# Sheet1.net
KiCad netlist of a schematic drawn in Altium Designer
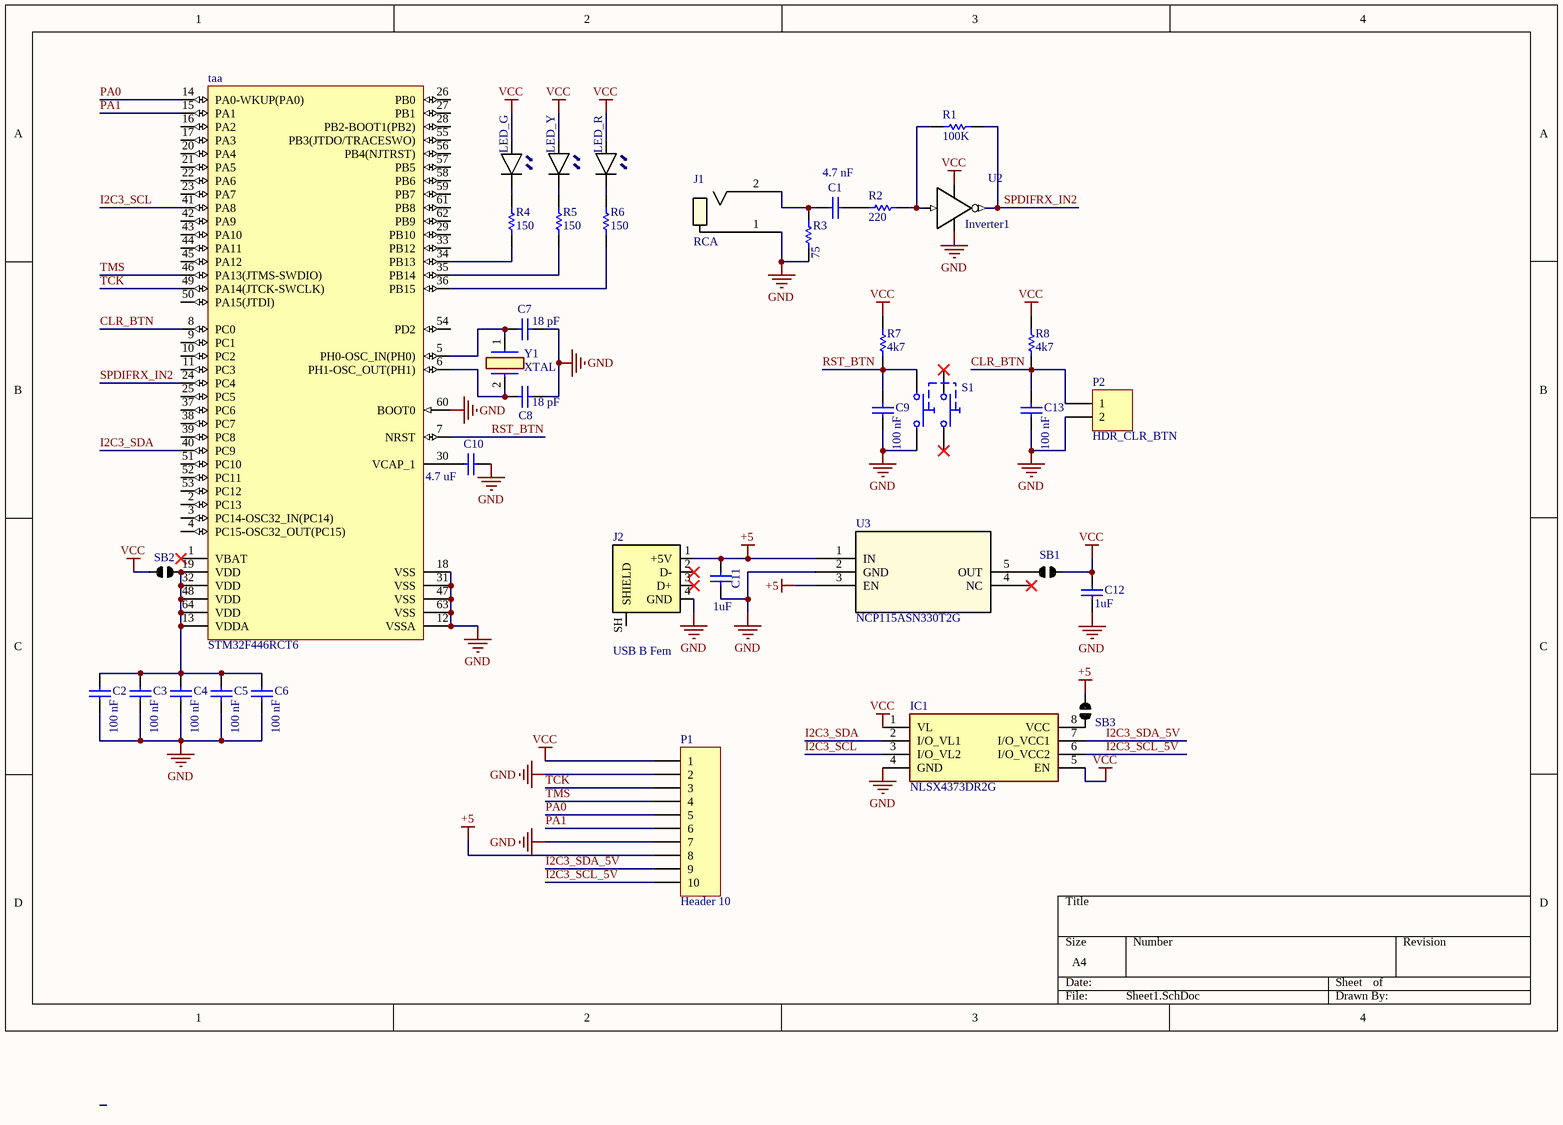
[diagram p0: Sheet1.SchDoc]

(export (version "E")
  (design (tool "Eeschema 10.0.6"))
  (components
    (comp (ref "C1")
      (value "4.7 nF")
      (footprint "RESC3216X70N")
      (description "Capacitor")
      (fields (field (name "Comment") "Cap") (field (name "PUBLISHER") "Altium Limited"))
      (libsource (lib "Miscellaneous Devices") (part "Cap"))
    )
    (comp (ref "C2")
      (value "100 nF")
      (footprint "RESC3216X70N")
      (description "Capacitor")
      (fields (field (name "Comment") "Cap") (field (name "PUBLISHER") "Altium Limited"))
      (libsource (lib "Miscellaneous Devices") (part "Cap"))
    )
    (comp (ref "C3")
      (value "100 nF")
      (footprint "RESC3216X70N")
      (description "Capacitor")
      (fields (field (name "Comment") "Cap") (field (name "PUBLISHER") "Altium Limited"))
      (libsource (lib "Miscellaneous Devices") (part "Cap"))
    )
    (comp (ref "C4")
      (value "100 nF")
      (footprint "RESC3216X70N")
      (description "Capacitor")
      (fields (field (name "Comment") "Cap") (field (name "PUBLISHER") "Altium Limited"))
      (libsource (lib "Miscellaneous Devices") (part "Cap"))
    )
    (comp (ref "C5")
      (value "100 nF")
      (footprint "RESC3216X70N")
      (description "Capacitor")
      (fields (field (name "Comment") "Cap") (field (name "PUBLISHER") "Altium Limited"))
      (libsource (lib "Miscellaneous Devices") (part "Cap"))
    )
    (comp (ref "C6")
      (value "100 nF")
      (footprint "RESC3216X70N")
      (description "Capacitor")
      (fields (field (name "Comment") "Cap") (field (name "PUBLISHER") "Altium Limited"))
      (libsource (lib "Miscellaneous Devices") (part "Cap"))
    )
    (comp (ref "C7")
      (value "18 pF")
      (footprint "RESC3216X70N")
      (description "Capacitor")
      (fields (field (name "Comment") "Cap") (field (name "PUBLISHER") "Altium Limited"))
      (libsource (lib "Miscellaneous Devices") (part "Cap"))
    )
    (comp (ref "C8")
      (value "18 pF")
      (footprint "RESC3216X70N")
      (description "Capacitor")
      (fields (field (name "Comment") "Cap") (field (name "PUBLISHER") "Altium Limited"))
      (libsource (lib "Miscellaneous Devices") (part "Cap"))
    )
    (comp (ref "C9")
      (value "100 nF")
      (footprint "RESC3216X70N")
      (description "Capacitor")
      (fields (field (name "Comment") "Cap") (field (name "PUBLISHER") "Altium Limited"))
      (libsource (lib "Miscellaneous Devices") (part "Cap"))
    )
    (comp (ref "C10")
      (value "4.7 uF")
      (footprint "CAPPRD250W50D655H1250")
      (description "Capacitor")
      (fields (field (name "Comment") "Cap") (field (name "PUBLISHER") "Altium Limited"))
      (libsource (lib "Miscellaneous Devices") (part "Cap"))
    )
    (comp (ref "C11")
      (value "1uF")
      (footprint "CAPPRD250W50D655H1250")
      (description "Capacitor")
      (fields (field (name "Comment") "Cap") (field (name "PUBLISHER") "Altium Limited"))
      (libsource (lib "Miscellaneous Devices") (part "Cap"))
    )
    (comp (ref "C12")
      (value "1uF")
      (footprint "CAPPRD250W50D655H1250")
      (description "Capacitor")
      (fields (field (name "Comment") "Cap") (field (name "PUBLISHER") "Altium Limited"))
      (libsource (lib "Miscellaneous Devices") (part "Cap"))
    )
    (comp (ref "C13")
      (value "100 nF")
      (footprint "RESC3216X70N")
      (description "Capacitor")
      (fields (field (name "Comment") "Cap") (field (name "PUBLISHER") "Altium Limited"))
      (libsource (lib "Miscellaneous Devices") (part "Cap"))
    )
    (comp (ref "IC1")
      (value "NLSX4373DR2G")
      (footprint "SamacSys:SOIC127P600X175-8N")
      (description "Integrated Circuit")
      (fields (field (name "MOUSER PART NUMBER") "863-NLSX4373DR2G"))
      (libsource (lib "*") (part "NLSX4373DR2G"))
    )
    (comp (ref "J1")
      (value "RCA")
      (footprint "KLPX-0848A-2-B_KYC")
      (description "No Description Available")
      (fields
        (field (name "MANUFACTURER_PART_NUMBER") "KLPX-0848A-2-B")
        (field (name "COPYRIGHT") "Copyright (C) 2023 Ultra Librarian. All rights reserved.")
      )
      (libsource (lib "KLPX-0848A-2-B") (part "KLPX-0848A-2-B"))
    )
    (comp (ref "J2") (value "USB B Fem") (footprint "UJ2BH1TH") (libsource (lib "USB") (part "USB B Fem")))
    (comp (ref "LED_G")
      (value "fucking led maat hoe moeilijk ist kutprogram")
      (footprint "LED_SSL-LX4673GD-LA20")
      (libsource (lib "Schlib1") (part "fucking led maat hoe moeilijk ist kutprogram"))
    )
    (comp (ref "LED_R")
      (value "fucking led maat hoe moeilijk ist kutprogram")
      (footprint "LED_SSL-LX4673GD-LA20")
      (libsource (lib "Schlib1") (part "fucking led maat hoe moeilijk ist kutprogram"))
    )
    (comp (ref "LED_Y")
      (value "fucking led maat hoe moeilijk ist kutprogram")
      (footprint "LED_SSL-LX4673GD-LA20")
      (libsource (lib "Schlib1") (part "fucking led maat hoe moeilijk ist kutprogram"))
    )
    (comp (ref "P1")
      (value "Header 10")
      (footprint "HDR1X10")
      (description "Header, 10-Pin")
      (fields (field (name "PUBLISHER") "Altium Limited"))
      (libsource (lib "Miscellaneous Connectors") (part "Header 10"))
    )
    (comp (ref "P2")
      (value "HDR_CLR_BTN")
      (footprint "HDR1X2")
      (description "Header, 2-Pin")
      (fields (field (name "PUBLISHER") "Altium Limited"))
      (libsource (lib "Miscellaneous Connectors") (part "Header 2"))
    )
    (comp (ref "R1")
      (value "100K")
      (footprint "RESC3216X70N")
      (description "Resistor")
      (fields (field (name "Comment") "Res1") (field (name "PUBLISHER") "Altium Limited"))
      (libsource (lib "Miscellaneous Devices") (part "Res1"))
    )
    (comp (ref "R2")
      (value "220")
      (footprint "RESC3216X70N")
      (description "Resistor")
      (fields (field (name "Comment") "Res1") (field (name "PUBLISHER") "Altium Limited"))
      (libsource (lib "Miscellaneous Devices") (part "Res1"))
    )
    (comp (ref "R3")
      (value "75")
      (footprint "RESC3216X70N")
      (description "Resistor")
      (fields (field (name "Comment") "Res1") (field (name "PUBLISHER") "Altium Limited"))
      (libsource (lib "Miscellaneous Devices") (part "Res1"))
    )
    (comp (ref "R4")
      (value "150")
      (footprint "RESC3216X70N")
      (description "Resistor")
      (fields (field (name "Comment") "Res1") (field (name "PUBLISHER") "Altium Limited"))
      (libsource (lib "Miscellaneous Devices") (part "Res1"))
    )
    (comp (ref "R5")
      (value "150")
      (footprint "RESC3216X70N")
      (description "Resistor")
      (fields (field (name "Comment") "Res1") (field (name "PUBLISHER") "Altium Limited"))
      (libsource (lib "Miscellaneous Devices") (part "Res1"))
    )
    (comp (ref "R6")
      (value "150")
      (footprint "RESC3216X70N")
      (description "Resistor")
      (fields (field (name "Comment") "Res1") (field (name "PUBLISHER") "Altium Limited"))
      (libsource (lib "Miscellaneous Devices") (part "Res1"))
    )
    (comp (ref "R7")
      (value "4k7")
      (footprint "RESC3216X70N")
      (description "Resistor")
      (fields (field (name "Comment") "Res1") (field (name "PUBLISHER") "Altium Limited"))
      (libsource (lib "Miscellaneous Devices") (part "Res1"))
    )
    (comp (ref "R8")
      (value "4k7")
      (footprint "RESC3216X70N")
      (description "Resistor")
      (fields (field (name "Comment") "Res1") (field (name "PUBLISHER") "Altium Limited"))
      (libsource (lib "Miscellaneous Devices") (part "Res1"))
    )
    (comp (ref "S1")
      (value "Doubl-Pole, Single-Throw Button")
      (footprint "TS026655BK160LCRD")
      (libsource (lib "Simulation Generic Components") (part "DPST Push Button"))
    )
    (comp (ref "SB1")
      (value "Solder Bridge")
      (footprint "Solder Bridge")
      (libsource (lib "schematic") (part "Solder Bridge"))
    )
    (comp (ref "SB2")
      (value "Solder Bridge")
      (footprint "Solder Bridge")
      (libsource (lib "schematic") (part "Solder Bridge"))
    )
    (comp (ref "SB3")
      (value "Solder Bridge")
      (footprint "Solder Bridge")
      (libsource (lib "") (part "Solder Bridge_1"))
    )
    (comp (ref "taa")
      (value "STM32F446RCT6")
      (footprint "STM-LQFP64_L")
      (libsource (lib "Altium Content Vault") (part "MC-ARM-STM32F446-LQFP64"))
    )
    (comp (ref "U2") (value "Inverter1") (footprint "DBV5-M") (libsource (lib "Schlib1") (part "Inverter1")))
    (comp (ref "U3")
      (value "NCP115ASN330T2G")
      (footprint "SOT95P275X120-5N")
      (description "No Description Available")
      (fields (field (name "COPYRIGHT") "Copyright (C) 2023 Ultra Librarian. All rights reserved."))
      (libsource (lib "NCP115ASN330T2G") (part "NCP115ASN330T2G"))
    )
    (comp (ref "Y1")
      (value "XTAL")
      (footprint "SamacSys:ECS80185PXGMTR")
      (description "Crystal or Oscillator")
      (fields
        (field (name "MANUFACTURER_PART_NUMBER") "ECS-80-18-5PX-GM-TR")
        (field (name "MOUSER PART NUMBER") "520-80-18-5PX-GM-TR")
      )
      (libsource (lib "Schlib1") (part "ECS-80-18-5PX-GM-TR"))
    )
  )
  (nets
    (net (code "1") (name "+5") (class "Default")
      (node (ref "C11") (pin "2") (pinfunction "2_2") (pintype "passive"))
      (node (ref "J2") (pin "1") (pinfunction "+5V_1") (pintype "power_in"))
      (node (ref "P1") (pin "8") (pinfunction "8_8") (pintype "passive"))
      (node (ref "SB3") (pin "2") (pinfunction "3_2") (pintype "passive"))
      (node (ref "U3") (pin "1") (pinfunction "IN_1") (pintype "passive"))
      (node (ref "U3") (pin "3") (pinfunction "EN_3") (pintype "passive"))
    )
    (net (code "2") (name "/CLR_BTN") (class "Default")
      (node (ref "C13") (pin "2") (pinfunction "2_2") (pintype "passive"))
      (node (ref "P2") (pin "1") (pinfunction "1_1") (pintype "passive"))
      (node (ref "R8") (pin "2") (pinfunction "2_2") (pintype "passive"))
      (node (ref "taa") (pin "8") (pinfunction "PC0_8") (pintype "bidirectional"))
    )
    (net (code "3") (name "/I2C3_SCL") (class "Default")
      (node (ref "IC1") (pin "3") (pinfunction "I/O_VL2_3") (pintype "passive"))
      (node (ref "taa") (pin "41") (pinfunction "PA8_41") (pintype "bidirectional"))
    )
    (net (code "4") (name "/I2C3_SCL_5V") (class "Default")
      (node (ref "IC1") (pin "6") (pinfunction "I/O_VCC2_6") (pintype "passive"))
      (node (ref "P1") (pin "10") (pinfunction "10_10") (pintype "passive"))
    )
    (net (code "5") (name "/I2C3_SDA") (class "Default")
      (node (ref "IC1") (pin "2") (pinfunction "I/O_VL1_2") (pintype "passive"))
      (node (ref "taa") (pin "40") (pinfunction "PC9_40") (pintype "bidirectional"))
    )
    (net (code "6") (name "/I2C3_SDA_5V") (class "Default")
      (node (ref "IC1") (pin "7") (pinfunction "I/O_VCC1_7") (pintype "passive"))
      (node (ref "P1") (pin "9") (pinfunction "9_9") (pintype "passive"))
    )
    (net (code "7") (name "/PA0") (class "Default")
      (node (ref "P1") (pin "5") (pinfunction "5_5") (pintype "passive"))
      (node (ref "taa") (pin "14") (pinfunction "PA0-WKUP(PA0)_14") (pintype "bidirectional"))
    )
    (net (code "8") (name "/PA1") (class "Default")
      (node (ref "P1") (pin "6") (pinfunction "6_6") (pintype "passive"))
      (node (ref "taa") (pin "15") (pinfunction "PA1_15") (pintype "bidirectional"))
    )
    (net (code "9") (name "/RST_BTN") (class "Default")
      (node (ref "C9") (pin "2") (pinfunction "2_2") (pintype "passive"))
      (node (ref "R7") (pin "2") (pinfunction "2_2") (pintype "passive"))
      (node (ref "S1") (pin "3") (pinfunction "3_3") (pintype "passive"))
      (node (ref "taa") (pin "7") (pinfunction "NRST_7") (pintype "bidirectional"))
    )
    (net (code "10") (name "/SPDIFRX_IN2") (class "Default")
      (node (ref "R1") (pin "1") (pinfunction "1_1") (pintype "passive"))
      (node (ref "U2") (pin "4") (pinfunction "Y_4") (pintype "output"))
      (node (ref "taa") (pin "24") (pinfunction "PC4_24") (pintype "bidirectional"))
    )
    (net (code "11") (name "/TCK") (class "Default")
      (node (ref "P1") (pin "3") (pinfunction "3_3") (pintype "passive"))
      (node (ref "taa") (pin "49") (pinfunction "PA14(JTCK-SWCLK)_49") (pintype "bidirectional"))
    )
    (net (code "12") (name "/TMS") (class "Default")
      (node (ref "P1") (pin "4") (pinfunction "4_4") (pintype "passive"))
      (node (ref "taa") (pin "46") (pinfunction "PA13(JTMS-SWDIO)_46") (pintype "bidirectional"))
    )
    (net (code "13") (name "GND") (class "Default")
      (node (ref "C10") (pin "2") (pinfunction "2_2") (pintype "passive"))
      (node (ref "C11") (pin "1") (pinfunction "1_1") (pintype "passive"))
      (node (ref "C12") (pin "1") (pinfunction "1_1") (pintype "passive"))
      (node (ref "C13") (pin "1") (pinfunction "1_1") (pintype "passive"))
      (node (ref "C2") (pin "1") (pinfunction "1_1") (pintype "passive"))
      (node (ref "C3") (pin "1") (pinfunction "1_1") (pintype "passive"))
      (node (ref "C4") (pin "1") (pinfunction "1_1") (pintype "passive"))
      (node (ref "C5") (pin "1") (pinfunction "1_1") (pintype "passive"))
      (node (ref "C6") (pin "1") (pinfunction "1_1") (pintype "passive"))
      (node (ref "C7") (pin "2") (pinfunction "2_2") (pintype "passive"))
      (node (ref "C8") (pin "2") (pinfunction "2_2") (pintype "passive"))
      (node (ref "C9") (pin "1") (pinfunction "1_1") (pintype "passive"))
      (node (ref "IC1") (pin "4") (pinfunction "GND_4") (pintype "passive"))
      (node (ref "J1") (pin "1") (pinfunction "1_1") (pintype "passive"))
      (node (ref "J2") (pin "4") (pinfunction "GND_4") (pintype "passive"))
      (node (ref "P1") (pin "2") (pinfunction "2_2") (pintype "passive"))
      (node (ref "P1") (pin "7") (pinfunction "7_7") (pintype "passive"))
      (node (ref "P2") (pin "2") (pinfunction "2_2") (pintype "passive"))
      (node (ref "R3") (pin "1") (pinfunction "1_1") (pintype "passive"))
      (node (ref "S1") (pin "4") (pinfunction "4_4") (pintype "passive"))
      (node (ref "U2") (pin "3") (pinfunction "GND_3") (pintype "passive"))
      (node (ref "U3") (pin "2") (pinfunction "GND_2") (pintype "power_in"))
      (node (ref "taa") (pin "12") (pinfunction "VSSA_12") (pintype "power_in"))
      (node (ref "taa") (pin "18") (pinfunction "VSS_18") (pintype "power_in"))
      (node (ref "taa") (pin "31") (pinfunction "VSS_31") (pintype "power_in"))
      (node (ref "taa") (pin "47") (pinfunction "VSS_47") (pintype "power_in"))
      (node (ref "taa") (pin "60") (pinfunction "BOOT0_60") (pintype "input"))
      (node (ref "taa") (pin "63") (pinfunction "VSS_63") (pintype "power_in"))
    )
    (net (code "14") (name "Net-(C1-Pad1)") (class "Default")
      (node (ref "C1") (pin "1") (pinfunction "1_1") (pintype "passive"))
      (node (ref "J1") (pin "2") (pinfunction "2_2") (pintype "passive"))
      (node (ref "R3") (pin "2") (pinfunction "2_2") (pintype "passive"))
    )
    (net (code "15") (name "Net-(C1-Pad2)") (class "Default")
      (node (ref "C1") (pin "2") (pinfunction "2_2") (pintype "passive"))
      (node (ref "R2") (pin "2") (pinfunction "2_2") (pintype "passive"))
    )
    (net (code "16") (name "Net-(IC1-VCC)") (class "Default")
      (node (ref "IC1") (pin "8") (pinfunction "VCC_8") (pintype "passive"))
      (node (ref "SB3") (pin "1") (pinfunction "3_1") (pintype "passive"))
    )
    (net (code "17") (name "Net-(LED_G-Pad2)") (class "Default")
      (node (ref "LED_G") (pin "2") (pinfunction "2_2") (pintype "passive"))
      (node (ref "R4") (pin "1") (pinfunction "1_1") (pintype "passive"))
    )
    (net (code "18") (name "Net-(LED_R-Pad2)") (class "Default")
      (node (ref "LED_R") (pin "2") (pinfunction "2_2") (pintype "passive"))
      (node (ref "R6") (pin "1") (pinfunction "1_1") (pintype "passive"))
    )
    (net (code "19") (name "Net-(LED_Y-Pad2)") (class "Default")
      (node (ref "LED_Y") (pin "2") (pinfunction "2_2") (pintype "passive"))
      (node (ref "R5") (pin "1") (pinfunction "1_1") (pintype "passive"))
    )
    (net (code "20") (name "Net-(U2-A)") (class "Default")
      (node (ref "R1") (pin "2") (pinfunction "2_2") (pintype "passive"))
      (node (ref "R2") (pin "1") (pinfunction "1_1") (pintype "passive"))
      (node (ref "U2") (pin "2") (pinfunction "A_2") (pintype "input"))
    )
    (net (code "21") (name "Net-(U3-OUT)") (class "Default")
      (node (ref "SB1") (pin "1") (pinfunction "3_1") (pintype "passive"))
      (node (ref "U3") (pin "5") (pinfunction "OUT_5") (pintype "passive"))
    )
    (net (code "22") (name "Net-(taa-PB13)") (class "Default")
      (node (ref "R4") (pin "2") (pinfunction "2_2") (pintype "passive"))
      (node (ref "taa") (pin "34") (pinfunction "PB13_34") (pintype "bidirectional"))
    )
    (net (code "23") (name "Net-(taa-PB14)") (class "Default")
      (node (ref "R5") (pin "2") (pinfunction "2_2") (pintype "passive"))
      (node (ref "taa") (pin "35") (pinfunction "PB14_35") (pintype "bidirectional"))
    )
    (net (code "24") (name "Net-(taa-PB15)") (class "Default")
      (node (ref "R6") (pin "2") (pinfunction "2_2") (pintype "passive"))
      (node (ref "taa") (pin "36") (pinfunction "PB15_36") (pintype "bidirectional"))
    )
    (net (code "25") (name "Net-(taa-PH0-OSC_IN(PH0))") (class "Default")
      (node (ref "C7") (pin "1") (pinfunction "1_1") (pintype "passive"))
      (node (ref "Y1") (pin "1") (pinfunction "1_1") (pintype "passive"))
      (node (ref "taa") (pin "5") (pinfunction "PH0-OSC_IN(PH0)_5") (pintype "bidirectional"))
    )
    (net (code "26") (name "Net-(taa-PH1-OSC_OUT(PH1))") (class "Default")
      (node (ref "C8") (pin "1") (pinfunction "1_1") (pintype "passive"))
      (node (ref "Y1") (pin "2") (pinfunction "2_2") (pintype "passive"))
      (node (ref "taa") (pin "6") (pinfunction "PH1-OSC_OUT(PH1)_6") (pintype "bidirectional"))
    )
    (net (code "27") (name "Net-(taa-VCAP_1)") (class "Default")
      (node (ref "C10") (pin "1") (pinfunction "1_1") (pintype "passive"))
      (node (ref "taa") (pin "30") (pinfunction "VCAP_1_30") (pintype "passive"))
    )
    (net (code "28") (name "Net-(taa-VDDA)") (class "Default")
      (node (ref "C2") (pin "2") (pinfunction "2_2") (pintype "passive"))
      (node (ref "C3") (pin "2") (pinfunction "2_2") (pintype "passive"))
      (node (ref "C4") (pin "2") (pinfunction "2_2") (pintype "passive"))
      (node (ref "C5") (pin "2") (pinfunction "2_2") (pintype "passive"))
      (node (ref "C6") (pin "2") (pinfunction "2_2") (pintype "passive"))
      (node (ref "SB2") (pin "2") (pinfunction "3_2") (pintype "passive"))
      (node (ref "taa") (pin "13") (pinfunction "VDDA_13") (pintype "power_in"))
      (node (ref "taa") (pin "19") (pinfunction "VDD_19") (pintype "power_in"))
      (node (ref "taa") (pin "32") (pinfunction "VDD_32") (pintype "power_in"))
      (node (ref "taa") (pin "48") (pinfunction "VDD_48") (pintype "power_in"))
      (node (ref "taa") (pin "64") (pinfunction "VDD_64") (pintype "power_in"))
    )
    (net (code "29") (name "VCC") (class "Default")
      (node (ref "C12") (pin "2") (pinfunction "2_2") (pintype "passive"))
      (node (ref "IC1") (pin "1") (pinfunction "VL_1") (pintype "passive"))
      (node (ref "IC1") (pin "5") (pinfunction "EN_5") (pintype "passive"))
      (node (ref "LED_G") (pin "1") (pinfunction "1_1") (pintype "passive"))
      (node (ref "LED_R") (pin "1") (pinfunction "1_1") (pintype "passive"))
      (node (ref "LED_Y") (pin "1") (pinfunction "1_1") (pintype "passive"))
      (node (ref "P1") (pin "1") (pinfunction "1_1") (pintype "passive"))
      (node (ref "R7") (pin "1") (pinfunction "1_1") (pintype "passive"))
      (node (ref "R8") (pin "1") (pinfunction "1_1") (pintype "passive"))
      (node (ref "SB1") (pin "2") (pinfunction "3_2") (pintype "passive"))
      (node (ref "SB2") (pin "1") (pinfunction "3_1") (pintype "passive"))
      (node (ref "U2") (pin "5") (pinfunction "VCC_5") (pintype "passive"))
    )
    (net (code "30") (name "unconnected-(J2-D+-Pad3)") (class "Default")
      (node (ref "J2") (pin "3") (pinfunction "D+_3") (pintype "bidirectional+no_connect"))
    )
    (net (code "31") (name "unconnected-(J2-D--Pad2)") (class "Default")
      (node (ref "J2") (pin "2") (pinfunction "D-_2") (pintype "bidirectional+no_connect"))
    )
    (net (code "32") (name "unconnected-(J2-SHIELD-PadSH)") (class "Default")
      (node (ref "J2") (pin "SH") (pinfunction "SHIELD_SH") (pintype "passive"))
    )
    (net (code "33") (name "unconnected-(S1-Pad1)") (class "Default")
      (node (ref "S1") (pin "1") (pinfunction "1_1") (pintype "passive+no_connect"))
    )
    (net (code "34") (name "unconnected-(S1-Pad2)") (class "Default")
      (node (ref "S1") (pin "2") (pinfunction "2_2") (pintype "passive+no_connect"))
    )
    (net (code "35") (name "unconnected-(U3-NC-Pad4)") (class "Default")
      (node (ref "U3") (pin "4") (pinfunction "NC_4") (pintype "passive+no_connect"))
    )
    (net (code "36") (name "unconnected-(taa-PA2-Pad16)") (class "Default")
      (node (ref "taa") (pin "16") (pinfunction "PA2_16") (pintype "bidirectional"))
    )
    (net (code "37") (name "unconnected-(taa-PA3-Pad17)") (class "Default")
      (node (ref "taa") (pin "17") (pinfunction "PA3_17") (pintype "bidirectional"))
    )
    (net (code "38") (name "unconnected-(taa-PA4-Pad20)") (class "Default")
      (node (ref "taa") (pin "20") (pinfunction "PA4_20") (pintype "bidirectional"))
    )
    (net (code "39") (name "unconnected-(taa-PA5-Pad21)") (class "Default")
      (node (ref "taa") (pin "21") (pinfunction "PA5_21") (pintype "bidirectional"))
    )
    (net (code "40") (name "unconnected-(taa-PA6-Pad22)") (class "Default")
      (node (ref "taa") (pin "22") (pinfunction "PA6_22") (pintype "bidirectional"))
    )
    (net (code "41") (name "unconnected-(taa-PA7-Pad23)") (class "Default")
      (node (ref "taa") (pin "23") (pinfunction "PA7_23") (pintype "bidirectional"))
    )
    (net (code "42") (name "unconnected-(taa-PA9-Pad42)") (class "Default")
      (node (ref "taa") (pin "42") (pinfunction "PA9_42") (pintype "bidirectional"))
    )
    (net (code "43") (name "unconnected-(taa-PA10-Pad43)") (class "Default")
      (node (ref "taa") (pin "43") (pinfunction "PA10_43") (pintype "bidirectional"))
    )
    (net (code "44") (name "unconnected-(taa-PA11-Pad44)") (class "Default")
      (node (ref "taa") (pin "44") (pinfunction "PA11_44") (pintype "bidirectional"))
    )
    (net (code "45") (name "unconnected-(taa-PA12-Pad45)") (class "Default")
      (node (ref "taa") (pin "45") (pinfunction "PA12_45") (pintype "bidirectional"))
    )
    (net (code "46") (name "unconnected-(taa-PA15(JTDI)-Pad50)") (class "Default")
      (node (ref "taa") (pin "50") (pinfunction "PA15(JTDI)_50") (pintype "bidirectional"))
    )
    (net (code "47") (name "unconnected-(taa-PB0-Pad26)") (class "Default")
      (node (ref "taa") (pin "26") (pinfunction "PB0_26") (pintype "bidirectional"))
    )
    (net (code "48") (name "unconnected-(taa-PB1-Pad27)") (class "Default")
      (node (ref "taa") (pin "27") (pinfunction "PB1_27") (pintype "bidirectional"))
    )
    (net (code "49") (name "unconnected-(taa-PB2-BOOT1(PB2)-Pad28)") (class "Default")
      (node (ref "taa") (pin "28") (pinfunction "PB2-BOOT1(PB2)_28") (pintype "bidirectional"))
    )
    (net (code "50") (name "unconnected-(taa-PB3(JTDO{slash}TRACESWO)-Pad55)") (class "Default")
      (node (ref "taa") (pin "55") (pinfunction "PB3(JTDO/TRACESWO)_55") (pintype "bidirectional"))
    )
    (net (code "51") (name "unconnected-(taa-PB4(NJTRST)-Pad56)") (class "Default")
      (node (ref "taa") (pin "56") (pinfunction "PB4(NJTRST)_56") (pintype "bidirectional"))
    )
    (net (code "52") (name "unconnected-(taa-PB5-Pad57)") (class "Default")
      (node (ref "taa") (pin "57") (pinfunction "PB5_57") (pintype "bidirectional"))
    )
    (net (code "53") (name "unconnected-(taa-PB6-Pad58)") (class "Default")
      (node (ref "taa") (pin "58") (pinfunction "PB6_58") (pintype "bidirectional"))
    )
    (net (code "54") (name "unconnected-(taa-PB7-Pad59)") (class "Default")
      (node (ref "taa") (pin "59") (pinfunction "PB7_59") (pintype "bidirectional"))
    )
    (net (code "55") (name "unconnected-(taa-PB8-Pad61)") (class "Default")
      (node (ref "taa") (pin "61") (pinfunction "PB8_61") (pintype "bidirectional"))
    )
    (net (code "56") (name "unconnected-(taa-PB9-Pad62)") (class "Default")
      (node (ref "taa") (pin "62") (pinfunction "PB9_62") (pintype "bidirectional"))
    )
    (net (code "57") (name "unconnected-(taa-PB10-Pad29)") (class "Default")
      (node (ref "taa") (pin "29") (pinfunction "PB10_29") (pintype "bidirectional"))
    )
    (net (code "58") (name "unconnected-(taa-PB12-Pad33)") (class "Default")
      (node (ref "taa") (pin "33") (pinfunction "PB12_33") (pintype "bidirectional"))
    )
    (net (code "59") (name "unconnected-(taa-PC1-Pad9)") (class "Default")
      (node (ref "taa") (pin "9") (pinfunction "PC1_9") (pintype "bidirectional"))
    )
    (net (code "60") (name "unconnected-(taa-PC2-Pad10)") (class "Default")
      (node (ref "taa") (pin "10") (pinfunction "PC2_10") (pintype "bidirectional"))
    )
    (net (code "61") (name "unconnected-(taa-PC3-Pad11)") (class "Default")
      (node (ref "taa") (pin "11") (pinfunction "PC3_11") (pintype "bidirectional"))
    )
    (net (code "62") (name "unconnected-(taa-PC5-Pad25)") (class "Default")
      (node (ref "taa") (pin "25") (pinfunction "PC5_25") (pintype "bidirectional"))
    )
    (net (code "63") (name "unconnected-(taa-PC6-Pad37)") (class "Default")
      (node (ref "taa") (pin "37") (pinfunction "PC6_37") (pintype "bidirectional"))
    )
    (net (code "64") (name "unconnected-(taa-PC7-Pad38)") (class "Default")
      (node (ref "taa") (pin "38") (pinfunction "PC7_38") (pintype "bidirectional"))
    )
    (net (code "65") (name "unconnected-(taa-PC8-Pad39)") (class "Default")
      (node (ref "taa") (pin "39") (pinfunction "PC8_39") (pintype "bidirectional"))
    )
    (net (code "66") (name "unconnected-(taa-PC10-Pad51)") (class "Default")
      (node (ref "taa") (pin "51") (pinfunction "PC10_51") (pintype "bidirectional"))
    )
    (net (code "67") (name "unconnected-(taa-PC11-Pad52)") (class "Default")
      (node (ref "taa") (pin "52") (pinfunction "PC11_52") (pintype "bidirectional"))
    )
    (net (code "68") (name "unconnected-(taa-PC12-Pad53)") (class "Default")
      (node (ref "taa") (pin "53") (pinfunction "PC12_53") (pintype "bidirectional"))
    )
    (net (code "69") (name "unconnected-(taa-PC13-Pad2)") (class "Default")
      (node (ref "taa") (pin "2") (pinfunction "PC13_2") (pintype "bidirectional"))
    )
    (net (code "70") (name "unconnected-(taa-PC14-OSC32_IN(PC14)-Pad3)") (class "Default")
      (node (ref "taa") (pin "3") (pinfunction "PC14-OSC32_IN(PC14)_3") (pintype "bidirectional"))
    )
    (net (code "71") (name "unconnected-(taa-PC15-OSC32_OUT(PC15)-Pad4)") (class "Default")
      (node (ref "taa") (pin "4") (pinfunction "PC15-OSC32_OUT(PC15)_4") (pintype "bidirectional"))
    )
    (net (code "72") (name "unconnected-(taa-PD2-Pad54)") (class "Default")
      (node (ref "taa") (pin "54") (pinfunction "PD2_54") (pintype "bidirectional"))
    )
    (net (code "73") (name "unconnected-(taa-VBAT-Pad1)") (class "Default")
      (node (ref "taa") (pin "1") (pinfunction "VBAT_1") (pintype "power_in+no_connect"))
    )
  )
)
